# temoin.net
KiCad netlist of a schematic drawn in EAGLE
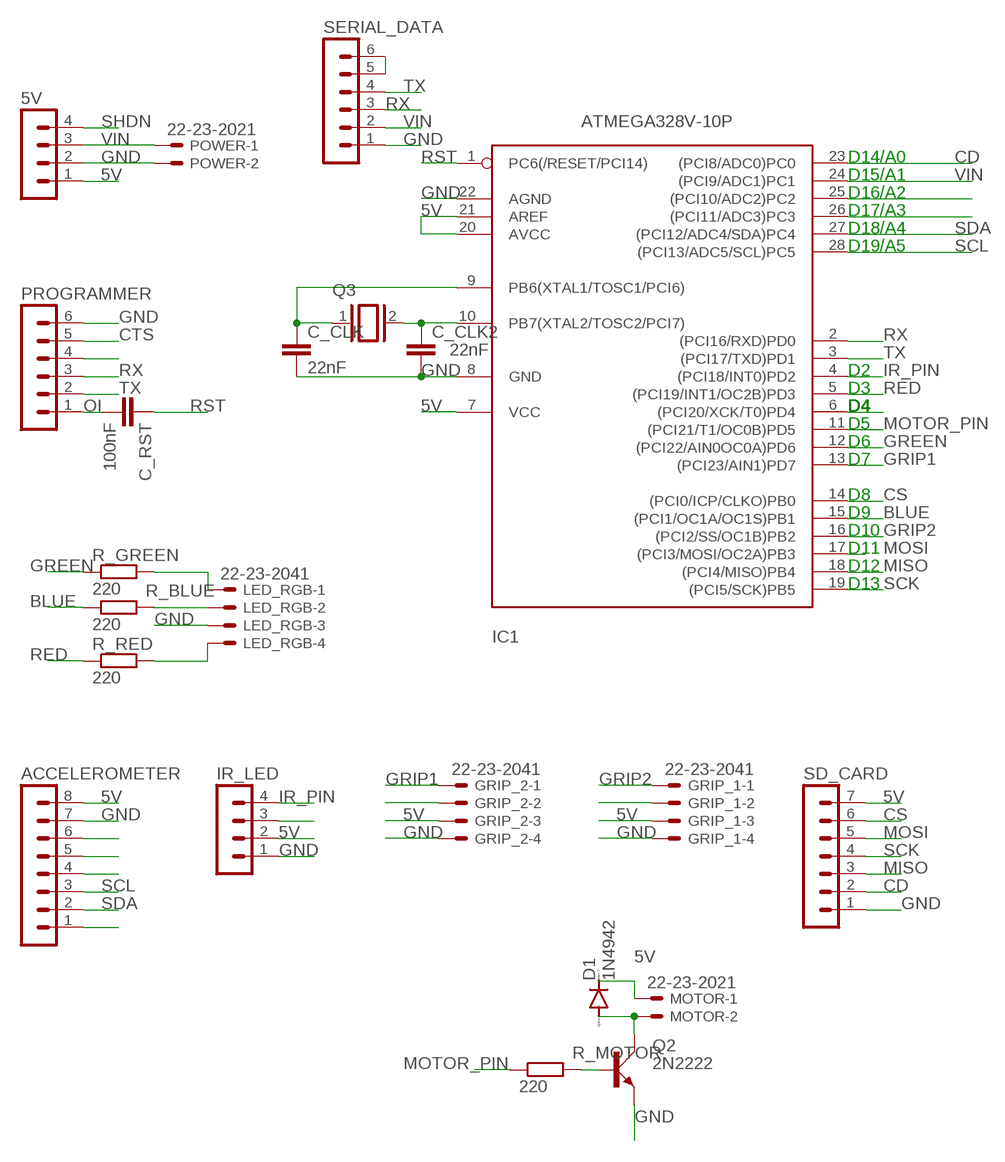
[diagram p0: schematic, sheet 1]

(export (version "E")
  (design (tool "Eeschema 10.0.6"))
  (components
    (comp (ref "5V")
      (value "MA04-1")
      (footprint "eagle-import:MA04-1")
      (libsource (lib "eagle-import") (part "MA04-1"))
    )
    (comp (ref "ACCELEROMETER")
      (value "MA08-1")
      (footprint "eagle-import:MA08-1")
      (libsource (lib "eagle-import") (part "MA08-1"))
    )
    (comp (ref "C_CLK")
      (value "22nF")
      (footprint "eagle-import:C025-025X050")
      (libsource (lib "eagle-import") (part "C-EU025-025X050"))
    )
    (comp (ref "C_CLK2")
      (value "22nF")
      (footprint "eagle-import:C025-025X050")
      (libsource (lib "eagle-import") (part "C-EU025-025X050"))
    )
    (comp (ref "C_RST")
      (value "100nF")
      (footprint "eagle-import:C025-040X050")
      (libsource (lib "eagle-import") (part "C-EU025-040X050"))
    )
    (comp (ref "D1")
      (value "1N4942")
      (footprint "eagle-import:DO41-10")
      (libsource (lib "eagle-import") (part "1N4942"))
    )
    (comp (ref "GRIP_1")
      (value "22-23-2041")
      (footprint "eagle-import:22-23-2041")
      (fields (field (name "MF") "MOLEX"))
      (libsource (lib "eagle-import") (part "22-23-2041"))
    )
    (comp (ref "GRIP_2")
      (value "22-23-2041")
      (footprint "eagle-import:22-23-2041")
      (fields (field (name "MF") "MOLEX"))
      (libsource (lib "eagle-import") (part "22-23-2041"))
    )
    (comp (ref "IC1")
      (value "ATMEGA328V-10P")
      (footprint "eagle-import:DIL28-3")
      (libsource (lib "eagle-import") (part "ATMEGA328PV-10"))
    )
    (comp (ref "IR_LED")
      (value "MA04-1")
      (footprint "eagle-import:MA04-1")
      (libsource (lib "eagle-import") (part "MA04-1"))
    )
    (comp (ref "LED_RGB")
      (value "22-23-2041")
      (footprint "eagle-import:22-23-2041")
      (fields (field (name "MF") "MOLEX"))
      (libsource (lib "eagle-import") (part "22-23-2041"))
    )
    (comp (ref "MOTOR")
      (value "22-23-2021")
      (footprint "eagle-import:22-23-2021")
      (fields (field (name "MF") "MOLEX"))
      (libsource (lib "eagle-import") (part "22-23-2021"))
    )
    (comp (ref "POWER")
      (value "22-23-2021")
      (footprint "eagle-import:22-23-2021")
      (fields (field (name "MF") "MOLEX"))
      (libsource (lib "eagle-import") (part "22-23-2021"))
    )
    (comp (ref "PROGRAMMER")
      (value "MA06-1")
      (footprint "eagle-import:MA06-1")
      (libsource (lib "eagle-import") (part "MA06-1"))
    )
    (comp (ref "Q2")
      (value "2N2222")
      (footprint "eagle-import:TO18A")
      (libsource (lib "eagle-import") (part "2N2222"))
    )
    (comp (ref "Q3")
      (value "XTAL/S")
      (footprint "eagle-import:QS")
      (libsource (lib "eagle-import") (part "XTAL/S"))
    )
    (comp (ref "R_BLUE")
      (value "220")
      (footprint "eagle-import:0411_12")
      (libsource (lib "eagle-import") (part "R-EU_0411/12"))
    )
    (comp (ref "R_GREEN")
      (value "220")
      (footprint "eagle-import:0411_12")
      (libsource (lib "eagle-import") (part "R-EU_0411/12"))
    )
    (comp (ref "R_MOTOR")
      (value "220")
      (footprint "eagle-import:0411_12")
      (libsource (lib "eagle-import") (part "R-EU_0411/12"))
    )
    (comp (ref "R_RED")
      (value "220")
      (footprint "eagle-import:0411_12")
      (libsource (lib "eagle-import") (part "R-EU_0411/12"))
    )
    (comp (ref "SD_CARD")
      (value "MA07-1")
      (footprint "eagle-import:MA07-1")
      (libsource (lib "eagle-import") (part "MA07-1"))
    )
    (comp (ref "SERIAL_DATA")
      (value "MA06-1")
      (footprint "eagle-import:MA06-1")
      (libsource (lib "eagle-import") (part "MA06-1"))
    )
  )
  (nets
    (net (code "1") (name "/5V") (class "Default")
      (node (ref "5V") (pin "1") (pinfunction "1_1") (pintype "passive"))
      (node (ref "ACCELEROMETER") (pin "8") (pinfunction "8_8") (pintype "passive"))
      (node (ref "D1") (pin "C") (pinfunction "C_C") (pintype "passive"))
      (node (ref "GRIP_1") (pin "3") (pinfunction "S_3") (pintype "passive"))
      (node (ref "GRIP_2") (pin "3") (pinfunction "S_3") (pintype "passive"))
      (node (ref "IC1") (pin "20") (pinfunction "AVCC_20") (pintype "bidirectional"))
      (node (ref "IC1") (pin "21") (pinfunction "AREF_21") (pintype "bidirectional"))
      (node (ref "IC1") (pin "7") (pinfunction "VCC_7") (pintype "bidirectional"))
      (node (ref "IR_LED") (pin "2") (pinfunction "2_2") (pintype "passive"))
      (node (ref "MOTOR") (pin "1") (pinfunction "S_1") (pintype "passive"))
      (node (ref "SD_CARD") (pin "7") (pinfunction "7_7") (pintype "passive"))
    )
    (net (code "2") (name "/BLUE") (class "Default")
      (node (ref "IC1") (pin "15") (pinfunction "(PCI1/OC1A/OC1S)PB1_15") (pintype "bidirectional"))
      (node (ref "R_BLUE") (pin "1") (pinfunction "1_1") (pintype "passive"))
    )
    (net (code "3") (name "/CD") (class "Default")
      (node (ref "IC1") (pin "23") (pinfunction "(PCI8/ADC0)PC0_23") (pintype "bidirectional"))
      (node (ref "SD_CARD") (pin "2") (pinfunction "2_2") (pintype "passive"))
    )
    (net (code "4") (name "/CS") (class "Default")
      (node (ref "IC1") (pin "14") (pinfunction "(PCI0/ICP/CLKO)PB0_14") (pintype "bidirectional"))
      (node (ref "SD_CARD") (pin "6") (pinfunction "6_6") (pintype "passive"))
    )
    (net (code "5") (name "/CTS") (class "Default")
      (node (ref "PROGRAMMER") (pin "5") (pinfunction "5_5") (pintype "passive"))
    )
    (net (code "6") (name "/GND") (class "Default")
      (node (ref "5V") (pin "2") (pinfunction "2_2") (pintype "passive"))
      (node (ref "ACCELEROMETER") (pin "7") (pinfunction "7_7") (pintype "passive"))
      (node (ref "C_CLK") (pin "2") (pinfunction "2_2") (pintype "passive"))
      (node (ref "C_CLK2") (pin "2") (pinfunction "2_2") (pintype "passive"))
      (node (ref "GRIP_1") (pin "4") (pinfunction "S_4") (pintype "passive"))
      (node (ref "GRIP_2") (pin "4") (pinfunction "S_4") (pintype "passive"))
      (node (ref "IC1") (pin "22") (pinfunction "AGND_22") (pintype "bidirectional"))
      (node (ref "IC1") (pin "8") (pinfunction "GND_8") (pintype "bidirectional"))
      (node (ref "IR_LED") (pin "1") (pinfunction "1_1") (pintype "passive"))
      (node (ref "LED_RGB") (pin "3") (pinfunction "S_3") (pintype "passive"))
      (node (ref "POWER") (pin "2") (pinfunction "S_2") (pintype "passive"))
      (node (ref "PROGRAMMER") (pin "6") (pinfunction "6_6") (pintype "passive"))
      (node (ref "Q2") (pin "E") (pinfunction "E_E") (pintype "passive"))
      (node (ref "SD_CARD") (pin "1") (pinfunction "1_1") (pintype "passive"))
      (node (ref "SERIAL_DATA") (pin "1") (pinfunction "1_1") (pintype "passive"))
    )
    (net (code "7") (name "/GREEN") (class "Default")
      (node (ref "IC1") (pin "12") (pinfunction "(PCI22/AIN0OC0A)PD6_12") (pintype "bidirectional"))
      (node (ref "R_GREEN") (pin "1") (pinfunction "1_1") (pintype "passive"))
    )
    (net (code "8") (name "/GRIP1") (class "Default")
      (node (ref "GRIP_2") (pin "1") (pinfunction "S_1") (pintype "passive"))
      (node (ref "IC1") (pin "13") (pinfunction "(PCI23/AIN1)PD7_13") (pintype "bidirectional"))
    )
    (net (code "9") (name "/GRIP2") (class "Default")
      (node (ref "GRIP_1") (pin "1") (pinfunction "S_1") (pintype "passive"))
      (node (ref "IC1") (pin "16") (pinfunction "(PCI2/SS/OC1B)PB2_16") (pintype "bidirectional"))
    )
    (net (code "10") (name "/IR_PIN") (class "Default")
      (node (ref "IC1") (pin "4") (pinfunction "(PCI18/INT0)PD2_4") (pintype "bidirectional"))
      (node (ref "IR_LED") (pin "4") (pinfunction "4_4") (pintype "passive"))
    )
    (net (code "11") (name "/MISO") (class "Default")
      (node (ref "IC1") (pin "18") (pinfunction "(PCI4/MISO)PB4_18") (pintype "bidirectional"))
      (node (ref "SD_CARD") (pin "3") (pinfunction "3_3") (pintype "passive"))
    )
    (net (code "12") (name "/MOSI") (class "Default")
      (node (ref "IC1") (pin "17") (pinfunction "(PCI3/MOSI/OC2A)PB3_17") (pintype "bidirectional"))
      (node (ref "SD_CARD") (pin "5") (pinfunction "5_5") (pintype "passive"))
    )
    (net (code "13") (name "/MOTOR_PIN") (class "Default")
      (node (ref "IC1") (pin "11") (pinfunction "(PCI21/T1/OC0B)PD5_11") (pintype "bidirectional"))
      (node (ref "R_MOTOR") (pin "1") (pinfunction "1_1") (pintype "passive"))
    )
    (net (code "14") (name "/OI") (class "Default")
      (node (ref "C_RST") (pin "2") (pinfunction "2_2") (pintype "passive"))
      (node (ref "PROGRAMMER") (pin "1") (pinfunction "1_1") (pintype "passive"))
    )
    (net (code "15") (name "/RED") (class "Default")
      (node (ref "IC1") (pin "5") (pinfunction "(PCI19/INT1/OC2B)PD3_5") (pintype "bidirectional"))
      (node (ref "R_RED") (pin "1") (pinfunction "1_1") (pintype "passive"))
    )
    (net (code "16") (name "/RST") (class "Default")
      (node (ref "C_RST") (pin "1") (pinfunction "1_1") (pintype "passive"))
      (node (ref "IC1") (pin "1") (pinfunction "PC6(/RESET/PCI14)_1") (pintype "bidirectional"))
    )
    (net (code "17") (name "/RX") (class "Default")
      (node (ref "IC1") (pin "2") (pinfunction "(PCI16/RXD)PD0_2") (pintype "bidirectional"))
      (node (ref "PROGRAMMER") (pin "3") (pinfunction "3_3") (pintype "passive"))
      (node (ref "SERIAL_DATA") (pin "3") (pinfunction "3_3") (pintype "passive"))
    )
    (net (code "18") (name "/SCK") (class "Default")
      (node (ref "IC1") (pin "19") (pinfunction "(PCI5/SCK)PB5_19") (pintype "bidirectional"))
      (node (ref "SD_CARD") (pin "4") (pinfunction "4_4") (pintype "passive"))
    )
    (net (code "19") (name "/SCL") (class "Default")
      (node (ref "ACCELEROMETER") (pin "3") (pinfunction "3_3") (pintype "passive"))
      (node (ref "IC1") (pin "28") (pinfunction "(PCI13/ADC5/SCL)PC5_28") (pintype "bidirectional"))
    )
    (net (code "20") (name "/SDA") (class "Default")
      (node (ref "ACCELEROMETER") (pin "2") (pinfunction "2_2") (pintype "passive"))
      (node (ref "IC1") (pin "27") (pinfunction "(PCI12/ADC4/SDA)PC4_27") (pintype "bidirectional"))
    )
    (net (code "21") (name "/SHDN") (class "Default")
      (node (ref "5V") (pin "4") (pinfunction "4_4") (pintype "passive"))
    )
    (net (code "22") (name "/TX") (class "Default")
      (node (ref "IC1") (pin "3") (pinfunction "(PCI17/TXD)PD1_3") (pintype "bidirectional"))
      (node (ref "PROGRAMMER") (pin "2") (pinfunction "2_2") (pintype "passive"))
      (node (ref "SERIAL_DATA") (pin "4") (pinfunction "4_4") (pintype "passive"))
    )
    (net (code "23") (name "/VIN") (class "Default")
      (node (ref "5V") (pin "3") (pinfunction "3_3") (pintype "passive"))
      (node (ref "IC1") (pin "24") (pinfunction "(PCI9/ADC1)PC1_24") (pintype "bidirectional"))
      (node (ref "POWER") (pin "1") (pinfunction "S_1") (pintype "passive"))
      (node (ref "SERIAL_DATA") (pin "2") (pinfunction "2_2") (pintype "passive"))
    )
    (net (code "24") (name "Net-(IC1-PB6(XTAL1{slash}TOSC1{slash}PCI6))") (class "Default")
      (node (ref "C_CLK") (pin "1") (pinfunction "1_1") (pintype "passive"))
      (node (ref "IC1") (pin "9") (pinfunction "PB6(XTAL1/TOSC1/PCI6)_9") (pintype "bidirectional"))
      (node (ref "Q3") (pin "1") (pinfunction "1_1") (pintype "passive"))
    )
    (net (code "25") (name "Net-(IC1-PB7(XTAL2{slash}TOSC2{slash}PCI7))") (class "Default")
      (node (ref "C_CLK2") (pin "1") (pinfunction "1_1") (pintype "passive"))
      (node (ref "IC1") (pin "10") (pinfunction "PB7(XTAL2/TOSC2/PCI7)_10") (pintype "bidirectional"))
      (node (ref "Q3") (pin "2") (pinfunction "2_2") (pintype "passive"))
    )
    (net (code "26") (name "Net-(LED_RGBA-S)") (class "Default")
      (node (ref "LED_RGB") (pin "1") (pinfunction "S_1") (pintype "passive"))
      (node (ref "R_GREEN") (pin "2") (pinfunction "2_2") (pintype "passive"))
    )
    (net (code "27") (name "Net-(LED_RGBB-S)") (class "Default")
      (node (ref "LED_RGB") (pin "2") (pinfunction "S_2") (pintype "passive"))
      (node (ref "R_BLUE") (pin "2") (pinfunction "2_2") (pintype "passive"))
    )
    (net (code "28") (name "Net-(LED_RGBD-S)") (class "Default")
      (node (ref "LED_RGB") (pin "4") (pinfunction "S_4") (pintype "passive"))
      (node (ref "R_RED") (pin "2") (pinfunction "2_2") (pintype "passive"))
    )
    (net (code "29") (name "Net-(MOTORB-S)") (class "Default")
      (node (ref "D1") (pin "A") (pinfunction "A_A") (pintype "passive"))
      (node (ref "MOTOR") (pin "2") (pinfunction "S_2") (pintype "passive"))
      (node (ref "Q2") (pin "C") (pinfunction "C_C") (pintype "passive"))
    )
    (net (code "30") (name "Net-(Q2-PadB)") (class "Default")
      (node (ref "Q2") (pin "B") (pinfunction "B_B") (pintype "passive"))
      (node (ref "R_MOTOR") (pin "2") (pinfunction "2_2") (pintype "passive"))
    )
    (net (code "31") (name "Net-(SERIAL_DATA-Pad5)") (class "Default")
      (node (ref "SERIAL_DATA") (pin "5") (pinfunction "5_5") (pintype "passive"))
      (node (ref "SERIAL_DATA") (pin "6") (pinfunction "6_6") (pintype "passive"))
    )
    (net (code "32") (name "unconnected-(ACCELEROMETER-Pad1)") (class "Default")
      (node (ref "ACCELEROMETER") (pin "1") (pinfunction "1_1") (pintype "passive"))
    )
    (net (code "33") (name "unconnected-(ACCELEROMETER-Pad4)") (class "Default")
      (node (ref "ACCELEROMETER") (pin "4") (pinfunction "4_4") (pintype "passive"))
    )
    (net (code "34") (name "unconnected-(ACCELEROMETER-Pad5)") (class "Default")
      (node (ref "ACCELEROMETER") (pin "5") (pinfunction "5_5") (pintype "passive"))
    )
    (net (code "35") (name "unconnected-(ACCELEROMETER-Pad6)") (class "Default")
      (node (ref "ACCELEROMETER") (pin "6") (pinfunction "6_6") (pintype "passive"))
    )
    (net (code "36") (name "unconnected-(GRIP_1B-S-Pad2)") (class "Default")
      (node (ref "GRIP_1") (pin "2") (pinfunction "S_2") (pintype "passive"))
    )
    (net (code "37") (name "unconnected-(GRIP_2B-S-Pad2)") (class "Default")
      (node (ref "GRIP_2") (pin "2") (pinfunction "S_2") (pintype "passive"))
    )
    (net (code "38") (name "unconnected-(IC1-(PCI10{slash}ADC2)PC2-Pad25)") (class "Default")
      (node (ref "IC1") (pin "25") (pinfunction "(PCI10/ADC2)PC2_25") (pintype "bidirectional"))
    )
    (net (code "39") (name "unconnected-(IC1-(PCI11{slash}ADC3)PC3-Pad26)") (class "Default")
      (node (ref "IC1") (pin "26") (pinfunction "(PCI11/ADC3)PC3_26") (pintype "bidirectional"))
    )
    (net (code "40") (name "unconnected-(IC1-(PCI20{slash}XCK{slash}T0)PD4-Pad6)") (class "Default")
      (node (ref "IC1") (pin "6") (pinfunction "(PCI20/XCK/T0)PD4_6") (pintype "bidirectional"))
    )
    (net (code "41") (name "unconnected-(IR_LED-Pad3)") (class "Default")
      (node (ref "IR_LED") (pin "3") (pinfunction "3_3") (pintype "passive"))
    )
    (net (code "42") (name "unconnected-(PROGRAMMER-Pad4)") (class "Default")
      (node (ref "PROGRAMMER") (pin "4") (pinfunction "4_4") (pintype "passive"))
    )
  )
)
